# HIC_Board.net
KiCad netlist of a schematic drawn in EAGLE
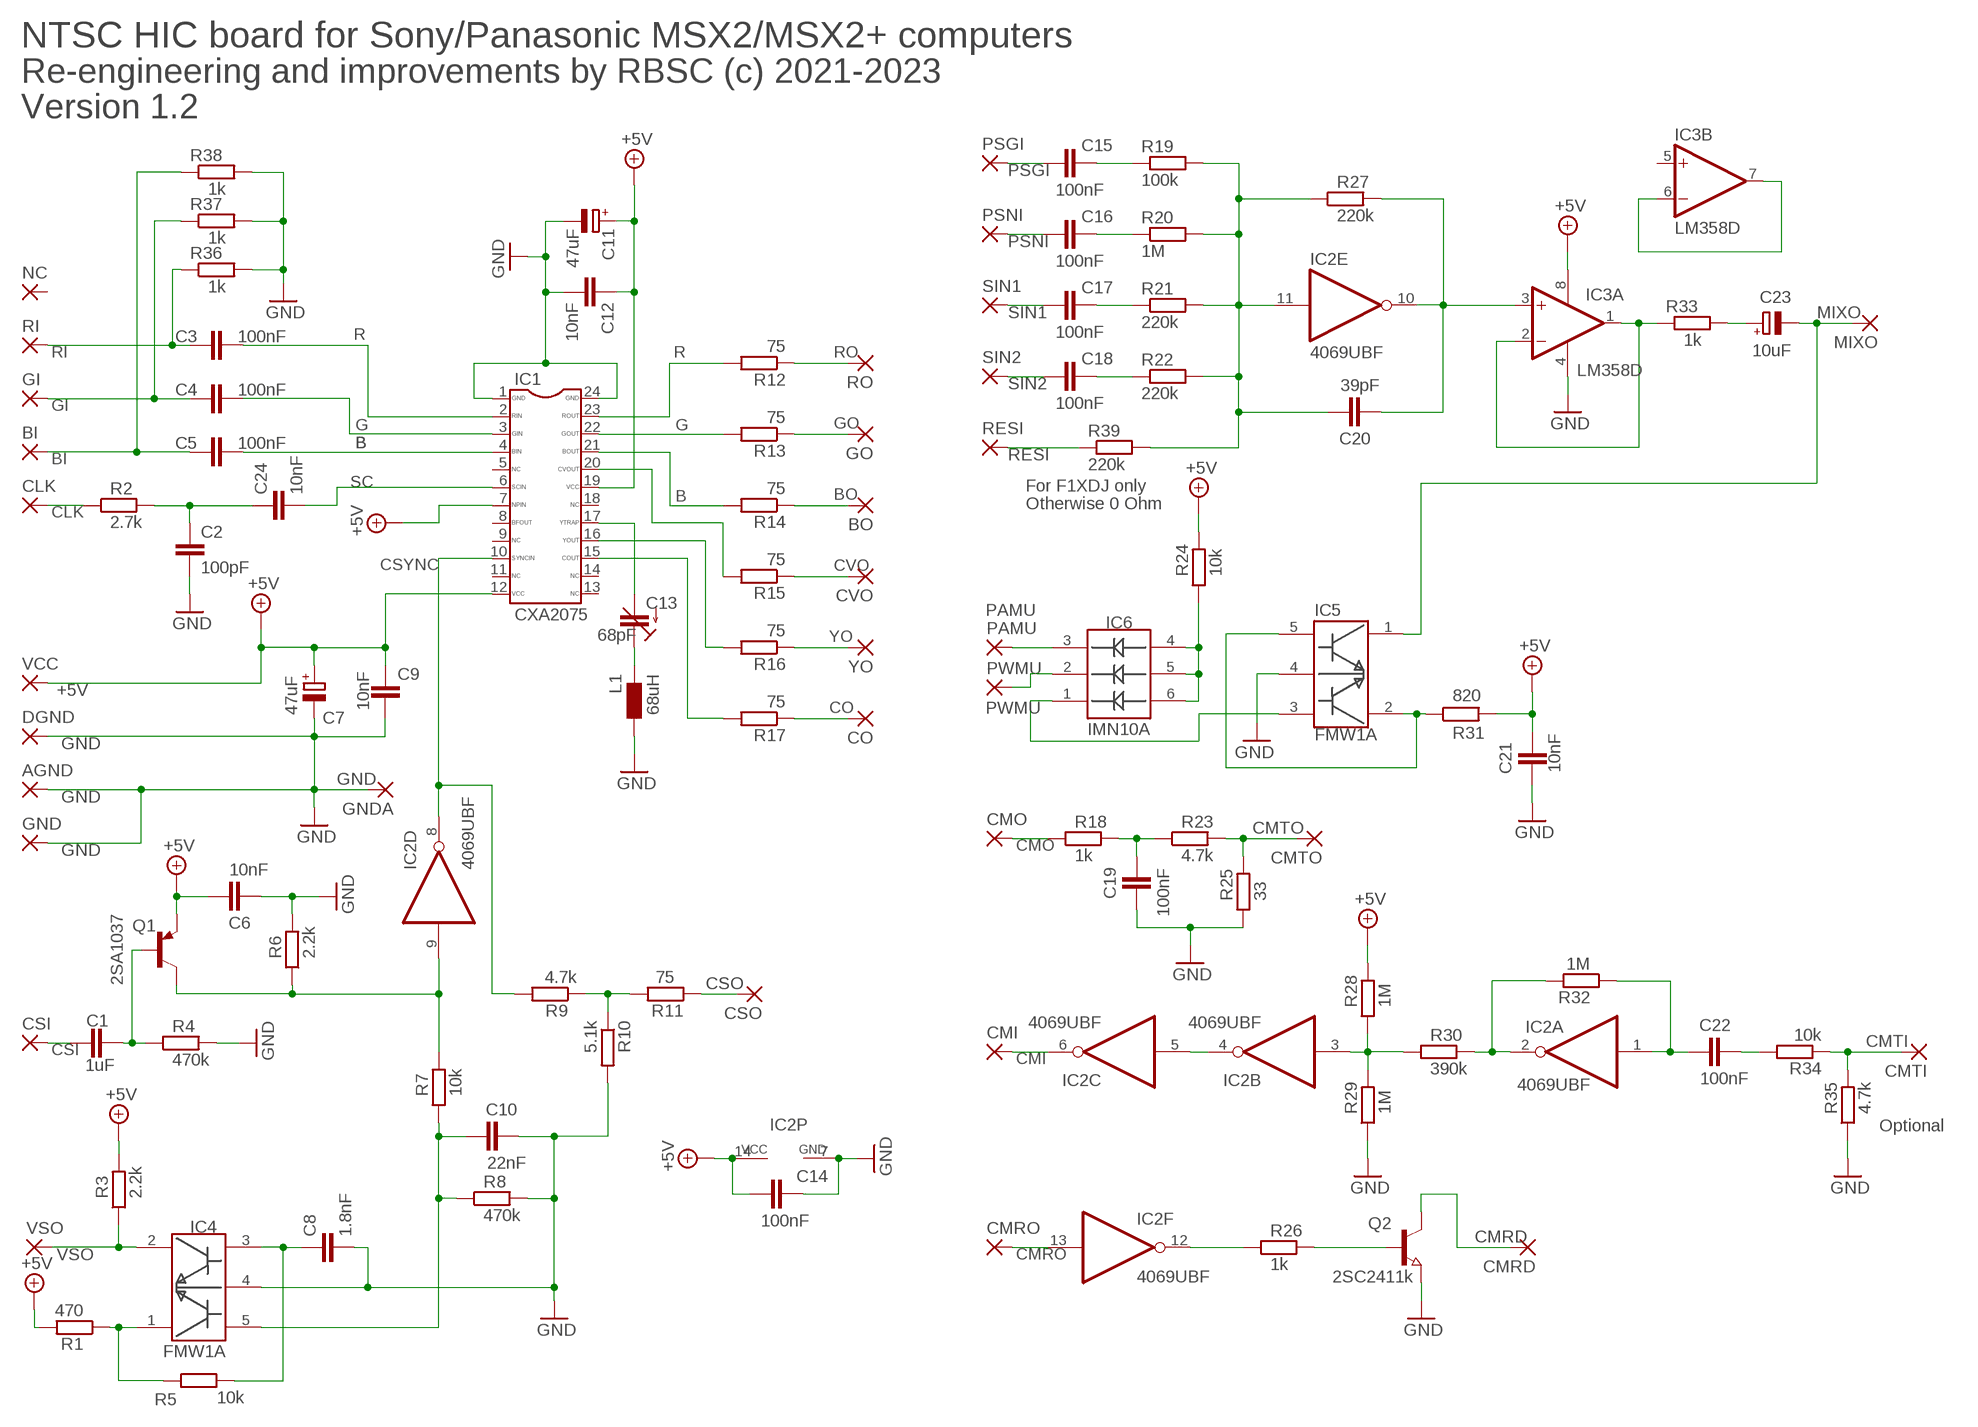
[diagram p0: schematic, sheet 1]

(export (version "E")
  (design (tool "Eeschema 10.0.6"))
  (components
    (comp (ref "AGND")
      (value "HICPADSMD")
      (footprint "eagle-import:SMD1,27-2,54")
      (libsource (lib "eagle-import") (part "HICPADSMD"))
    )
    (comp (ref "BI")
      (value "HICPADSMD")
      (footprint "eagle-import:SMD1,27-2,54")
      (libsource (lib "eagle-import") (part "HICPADSMD"))
    )
    (comp (ref "BO")
      (value "HICPADSMD")
      (footprint "eagle-import:SMD1,27-2,54")
      (libsource (lib "eagle-import") (part "HICPADSMD"))
    )
    (comp (ref "C1")
      (value "1uF")
      (footprint "eagle-import:C1210")
      (libsource (lib "eagle-import") (part "C-EUC1210"))
    )
    (comp (ref "C2")
      (value "100pF")
      (footprint "eagle-import:C0805")
      (libsource (lib "eagle-import") (part "C-EUC0805"))
    )
    (comp (ref "C3")
      (value "100nF")
      (footprint "eagle-import:C0805")
      (libsource (lib "eagle-import") (part "C-EUC0805"))
    )
    (comp (ref "C4")
      (value "100nF")
      (footprint "eagle-import:C0805")
      (libsource (lib "eagle-import") (part "C-EUC0805"))
    )
    (comp (ref "C5")
      (value "100nF")
      (footprint "eagle-import:C0805")
      (libsource (lib "eagle-import") (part "C-EUC0805"))
    )
    (comp (ref "C6")
      (value "10nF")
      (footprint "eagle-import:C0805")
      (libsource (lib "eagle-import") (part "C-EUC0805"))
    )
    (comp (ref "C7")
      (value "47uF")
      (footprint "eagle-import:SMC_B")
      (libsource (lib "eagle-import") (part "CPOL-EUSMCB"))
    )
    (comp (ref "C8")
      (value "1.8nF")
      (footprint "eagle-import:C0805")
      (libsource (lib "eagle-import") (part "C-EUC0805"))
    )
    (comp (ref "C9")
      (value "10nF")
      (footprint "eagle-import:C0805")
      (libsource (lib "eagle-import") (part "C-EUC0805"))
    )
    (comp (ref "C10")
      (value "22nF")
      (footprint "eagle-import:C0805")
      (libsource (lib "eagle-import") (part "C-EUC0805"))
    )
    (comp (ref "C11")
      (value "47uF")
      (footprint "eagle-import:SMC_B")
      (libsource (lib "eagle-import") (part "CPOL-EUSMCB"))
    )
    (comp (ref "C12")
      (value "10nF")
      (footprint "eagle-import:C0805")
      (libsource (lib "eagle-import") (part "C-EUC0805"))
    )
    (comp (ref "C13")
      (value "68pF")
      (footprint "eagle-import:CTRIMTZ03")
      (libsource (lib "eagle-import") (part "C-TRIMMTZ03"))
    )
    (comp (ref "C14")
      (value "100nF")
      (footprint "eagle-import:C0805")
      (libsource (lib "eagle-import") (part "C-EUC0805"))
    )
    (comp (ref "C15")
      (value "100nF")
      (footprint "eagle-import:C0805")
      (libsource (lib "eagle-import") (part "C-EUC0805"))
    )
    (comp (ref "C16")
      (value "100nF")
      (footprint "eagle-import:C0805")
      (libsource (lib "eagle-import") (part "C-EUC0805"))
    )
    (comp (ref "C17")
      (value "100nF")
      (footprint "eagle-import:C0805")
      (libsource (lib "eagle-import") (part "C-EUC0805"))
    )
    (comp (ref "C18")
      (value "100nF")
      (footprint "eagle-import:C0805")
      (libsource (lib "eagle-import") (part "C-EUC0805"))
    )
    (comp (ref "C19")
      (value "100nF")
      (footprint "eagle-import:C0805")
      (libsource (lib "eagle-import") (part "C-EUC0805"))
    )
    (comp (ref "C20")
      (value "39pF")
      (footprint "eagle-import:C0805")
      (libsource (lib "eagle-import") (part "C-EUC0805"))
    )
    (comp (ref "C21")
      (value "10nF")
      (footprint "eagle-import:C0805")
      (libsource (lib "eagle-import") (part "C-EUC0805"))
    )
    (comp (ref "C22")
      (value "100nF")
      (footprint "eagle-import:C0805")
      (libsource (lib "eagle-import") (part "C-EUC0805"))
    )
    (comp (ref "C23")
      (value "10uF")
      (footprint "eagle-import:SMC_B")
      (libsource (lib "eagle-import") (part "CPOL-EUSMCB"))
    )
    (comp (ref "C24")
      (value "10nF")
      (footprint "eagle-import:C0805")
      (libsource (lib "eagle-import") (part "C-EUC0805"))
    )
    (comp (ref "CLK")
      (value "HICPADSMD")
      (footprint "eagle-import:SMD1,27-2,54")
      (libsource (lib "eagle-import") (part "HICPADSMD"))
    )
    (comp (ref "CMI")
      (value "HICPADSMD")
      (footprint "eagle-import:SMD1,27-2,54")
      (libsource (lib "eagle-import") (part "HICPADSMD"))
    )
    (comp (ref "CMO")
      (value "HICPADSMD")
      (footprint "eagle-import:SMD1,27-2,54")
      (libsource (lib "eagle-import") (part "HICPADSMD"))
    )
    (comp (ref "CMRD")
      (value "HICPADSMD")
      (footprint "eagle-import:SMD1,27-2,54")
      (libsource (lib "eagle-import") (part "HICPADSMD"))
    )
    (comp (ref "CMRO")
      (value "HICPADSMD")
      (footprint "eagle-import:SMD1,27-2,54")
      (libsource (lib "eagle-import") (part "HICPADSMD"))
    )
    (comp (ref "CMTI")
      (value "HICPADSMD")
      (footprint "eagle-import:SMD1,27-2,54")
      (libsource (lib "eagle-import") (part "HICPADSMD"))
    )
    (comp (ref "CMTO")
      (value "HICPADSMD")
      (footprint "eagle-import:SMD1,27-2,54")
      (libsource (lib "eagle-import") (part "HICPADSMD"))
    )
    (comp (ref "CO")
      (value "HICPADSMD")
      (footprint "eagle-import:SMD1,27-2,54")
      (libsource (lib "eagle-import") (part "HICPADSMD"))
    )
    (comp (ref "CSI")
      (value "HICPADSMD")
      (footprint "eagle-import:SMD1,27-2,54")
      (libsource (lib "eagle-import") (part "HICPADSMD"))
    )
    (comp (ref "CSO")
      (value "HICPADSMD")
      (footprint "eagle-import:SMD1,27-2,54")
      (libsource (lib "eagle-import") (part "HICPADSMD"))
    )
    (comp (ref "CVO")
      (value "HICPADSMD")
      (footprint "eagle-import:SMD1,27-2,54")
      (libsource (lib "eagle-import") (part "HICPADSMD"))
    )
    (comp (ref "DGND")
      (value "HICPADSMD")
      (footprint "eagle-import:SMD1,27-2,54")
      (libsource (lib "eagle-import") (part "HICPADSMD"))
    )
    (comp (ref "GI")
      (value "HICPADSMD")
      (footprint "eagle-import:SMD1,27-2,54")
      (libsource (lib "eagle-import") (part "HICPADSMD"))
    )
    (comp (ref "GND")
      (value "HICPADSMD")
      (footprint "eagle-import:SMD1,27-2,54")
      (libsource (lib "eagle-import") (part "HICPADSMD"))
    )
    (comp (ref "GNDA")
      (value "HICPADSMD")
      (footprint "eagle-import:SMD1,27-2,54")
      (libsource (lib "eagle-import") (part "HICPADSMD"))
    )
    (comp (ref "GO")
      (value "HICPADSMD")
      (footprint "eagle-import:SMD1,27-2,54")
      (libsource (lib "eagle-import") (part "HICPADSMD"))
    )
    (comp (ref "IC1")
      (value "CXA2075")
      (footprint "eagle-import:SOP24")
      (libsource (lib "eagle-import") (part "CXA2075"))
    )
    (comp (ref "IC2")
      (value "4069UBF")
      (footprint "eagle-import:SO14")
      (libsource (lib "eagle-import") (part "7404DHCT"))
    )
    (comp (ref "IC3")
      (value "LM358D")
      (footprint "eagle-import:SO08")
      (libsource (lib "eagle-import") (part "LM358D"))
    )
    (comp (ref "IC4")
      (value "FMW1A")
      (footprint "eagle-import:SMT5")
      (libsource (lib "eagle-import") (part "FMW1A"))
    )
    (comp (ref "IC5")
      (value "FMW1A")
      (footprint "eagle-import:SMT5")
      (libsource (lib "eagle-import") (part "FMW1A"))
    )
    (comp (ref "IC6")
      (value "IMN10A")
      (footprint "eagle-import:SMT6")
      (libsource (lib "eagle-import") (part "IMN10A"))
    )
    (comp (ref "L1")
      (value "68uH")
      (footprint "eagle-import:L3225M")
      (libsource (lib "eagle-import") (part "LL3225M"))
    )
    (comp (ref "MIXO")
      (value "HICPADSMD")
      (footprint "eagle-import:SMD1,27-2,54")
      (libsource (lib "eagle-import") (part "HICPADSMD"))
    )
    (comp (ref "NC")
      (value "HICPADSMD")
      (footprint "eagle-import:SMD1,27-2,54")
      (libsource (lib "eagle-import") (part "HICPADSMD"))
    )
    (comp (ref "PAMU")
      (value "HICPADSMD")
      (footprint "eagle-import:SMD1,27-2,54")
      (libsource (lib "eagle-import") (part "HICPADSMD"))
    )
    (comp (ref "PSGI")
      (value "HICPADSMD")
      (footprint "eagle-import:SMD1,27-2,54")
      (libsource (lib "eagle-import") (part "HICPADSMD"))
    )
    (comp (ref "PSNI")
      (value "HICPADSMD")
      (footprint "eagle-import:SMD1,27-2,54")
      (libsource (lib "eagle-import") (part "HICPADSMD"))
    )
    (comp (ref "PWMU")
      (value "HICPADSMD")
      (footprint "eagle-import:SMD1,27-2,54")
      (libsource (lib "eagle-import") (part "HICPADSMD"))
    )
    (comp (ref "Q1")
      (value "2SA1037")
      (footprint "eagle-import:SOT23")
      (libsource (lib "eagle-import") (part "BCX71SMD"))
    )
    (comp (ref "Q2")
      (value "2SC2411k")
      (footprint "eagle-import:SOT23")
      (libsource (lib "eagle-import") (part "NPN-TRANSISTOR_SOT23"))
    )
    (comp (ref "R1")
      (value "470")
      (footprint "eagle-import:R0805")
      (libsource (lib "eagle-import") (part "R-EU_R0805"))
    )
    (comp (ref "R2")
      (value "2.7k")
      (footprint "eagle-import:R0805")
      (libsource (lib "eagle-import") (part "R-EU_R0805"))
    )
    (comp (ref "R3")
      (value "2.2k")
      (footprint "eagle-import:R0805")
      (libsource (lib "eagle-import") (part "R-EU_R0805"))
    )
    (comp (ref "R4")
      (value "470k")
      (footprint "eagle-import:R0805")
      (libsource (lib "eagle-import") (part "R-EU_R0805"))
    )
    (comp (ref "R5")
      (value "10k")
      (footprint "eagle-import:R0805")
      (libsource (lib "eagle-import") (part "R-EU_R0805"))
    )
    (comp (ref "R6")
      (value "2.2k")
      (footprint "eagle-import:R0805")
      (libsource (lib "eagle-import") (part "R-EU_R0805"))
    )
    (comp (ref "R7")
      (value "10k")
      (footprint "eagle-import:R0805")
      (libsource (lib "eagle-import") (part "R-EU_R0805"))
    )
    (comp (ref "R8")
      (value "470k")
      (footprint "eagle-import:R0805")
      (libsource (lib "eagle-import") (part "R-EU_R0805"))
    )
    (comp (ref "R9")
      (value "4.7k")
      (footprint "eagle-import:R0805")
      (libsource (lib "eagle-import") (part "R-EU_R0805"))
    )
    (comp (ref "R10")
      (value "5.1k")
      (footprint "eagle-import:R0805")
      (libsource (lib "eagle-import") (part "R-EU_R0805"))
    )
    (comp (ref "R11")
      (value "75")
      (footprint "eagle-import:R0805")
      (libsource (lib "eagle-import") (part "R-EU_R0805"))
    )
    (comp (ref "R12")
      (value "75")
      (footprint "eagle-import:R0805")
      (libsource (lib "eagle-import") (part "R-EU_R0805"))
    )
    (comp (ref "R13")
      (value "75")
      (footprint "eagle-import:R0805")
      (libsource (lib "eagle-import") (part "R-EU_R0805"))
    )
    (comp (ref "R14")
      (value "75")
      (footprint "eagle-import:R0805")
      (libsource (lib "eagle-import") (part "R-EU_R0805"))
    )
    (comp (ref "R15")
      (value "75")
      (footprint "eagle-import:R0805")
      (libsource (lib "eagle-import") (part "R-EU_R0805"))
    )
    (comp (ref "R16")
      (value "75")
      (footprint "eagle-import:R0805")
      (libsource (lib "eagle-import") (part "R-EU_R0805"))
    )
    (comp (ref "R17")
      (value "75")
      (footprint "eagle-import:R0805")
      (libsource (lib "eagle-import") (part "R-EU_R0805"))
    )
    (comp (ref "R18")
      (value "1k")
      (footprint "eagle-import:R0805")
      (libsource (lib "eagle-import") (part "R-EU_R0805"))
    )
    (comp (ref "R19")
      (value "100k")
      (footprint "eagle-import:R0805")
      (libsource (lib "eagle-import") (part "R-EU_R0805"))
    )
    (comp (ref "R20")
      (value "1M")
      (footprint "eagle-import:R0805")
      (libsource (lib "eagle-import") (part "R-EU_R0805"))
    )
    (comp (ref "R21")
      (value "220k")
      (footprint "eagle-import:R0805")
      (libsource (lib "eagle-import") (part "R-EU_R0805"))
    )
    (comp (ref "R22")
      (value "220k")
      (footprint "eagle-import:R0805")
      (libsource (lib "eagle-import") (part "R-EU_R0805"))
    )
    (comp (ref "R23")
      (value "4.7k")
      (footprint "eagle-import:R0805")
      (libsource (lib "eagle-import") (part "R-EU_R0805"))
    )
    (comp (ref "R24")
      (value "10k")
      (footprint "eagle-import:R0805")
      (libsource (lib "eagle-import") (part "R-EU_R0805"))
    )
    (comp (ref "R25")
      (value "33")
      (footprint "eagle-import:R0805")
      (libsource (lib "eagle-import") (part "R-EU_R0805"))
    )
    (comp (ref "R26")
      (value "1k")
      (footprint "eagle-import:R0805")
      (libsource (lib "eagle-import") (part "R-EU_R0805"))
    )
    (comp (ref "R27")
      (value "220k")
      (footprint "eagle-import:R0805")
      (libsource (lib "eagle-import") (part "R-EU_R0805"))
    )
    (comp (ref "R28")
      (value "1M")
      (footprint "eagle-import:R0805")
      (libsource (lib "eagle-import") (part "R-EU_R0805"))
    )
    (comp (ref "R29")
      (value "1M")
      (footprint "eagle-import:R0805")
      (libsource (lib "eagle-import") (part "R-EU_R0805"))
    )
    (comp (ref "R30")
      (value "390k")
      (footprint "eagle-import:R0805")
      (libsource (lib "eagle-import") (part "R-EU_R0805"))
    )
    (comp (ref "R31")
      (value "820")
      (footprint "eagle-import:R0805")
      (libsource (lib "eagle-import") (part "R-EU_R0805"))
    )
    (comp (ref "R32")
      (value "1M")
      (footprint "eagle-import:R0805")
      (libsource (lib "eagle-import") (part "R-EU_R0805"))
    )
    (comp (ref "R33")
      (value "1k")
      (footprint "eagle-import:R0805")
      (libsource (lib "eagle-import") (part "R-EU_R0805"))
    )
    (comp (ref "R34")
      (value "10k")
      (footprint "eagle-import:R0805")
      (libsource (lib "eagle-import") (part "R-EU_R0805"))
    )
    (comp (ref "R35")
      (value "4.7k")
      (footprint "eagle-import:R0805")
      (libsource (lib "eagle-import") (part "R-EU_R0805"))
    )
    (comp (ref "R36")
      (value "1k")
      (footprint "eagle-import:R0805")
      (libsource (lib "eagle-import") (part "R-EU_R0805"))
    )
    (comp (ref "R37")
      (value "1k")
      (footprint "eagle-import:R0805")
      (libsource (lib "eagle-import") (part "R-EU_R0805"))
    )
    (comp (ref "R38")
      (value "1k")
      (footprint "eagle-import:R0805")
      (libsource (lib "eagle-import") (part "R-EU_R0805"))
    )
    (comp (ref "R39")
      (value "220k")
      (footprint "eagle-import:R0805")
      (libsource (lib "eagle-import") (part "R-EU_R0805"))
    )
    (comp (ref "RESI")
      (value "HICPADSMD")
      (footprint "eagle-import:SMD1,27-2,54")
      (libsource (lib "eagle-import") (part "HICPADSMD"))
    )
    (comp (ref "RI")
      (value "HICPADSMD")
      (footprint "eagle-import:SMD1,27-2,54")
      (libsource (lib "eagle-import") (part "HICPADSMD"))
    )
    (comp (ref "RO")
      (value "HICPADSMD")
      (footprint "eagle-import:SMD1,27-2,54")
      (libsource (lib "eagle-import") (part "HICPADSMD"))
    )
    (comp (ref "SIN1")
      (value "HICPADSMD")
      (footprint "eagle-import:SMD1,27-2,54")
      (libsource (lib "eagle-import") (part "HICPADSMD"))
    )
    (comp (ref "SIN2")
      (value "HICPADSMD")
      (footprint "eagle-import:SMD1,27-2,54")
      (libsource (lib "eagle-import") (part "HICPADSMD"))
    )
    (comp (ref "VCC")
      (value "HICPADSMD")
      (footprint "eagle-import:SMD1,27-2,54")
      (libsource (lib "eagle-import") (part "HICPADSMD"))
    )
    (comp (ref "VSO")
      (value "HICPADSMD")
      (footprint "eagle-import:SMD1,27-2,54")
      (libsource (lib "eagle-import") (part "HICPADSMD"))
    )
    (comp (ref "YO")
      (value "HICPADSMD")
      (footprint "eagle-import:SMD1,27-2,54")
      (libsource (lib "eagle-import") (part "HICPADSMD"))
    )
  )
  (nets
    (net (code "1") (name "+5V") (class "Default")
      (node (ref "C11") (pin "+") (pinfunction "+_+") (pintype "passive"))
      (node (ref "C12") (pin "1") (pinfunction "1_1") (pintype "passive"))
      (node (ref "C14") (pin "2") (pinfunction "2_2") (pintype "passive"))
      (node (ref "C21") (pin "2") (pinfunction "2_2") (pintype "passive"))
      (node (ref "C6") (pin "1") (pinfunction "1_1") (pintype "passive"))
      (node (ref "C7") (pin "+") (pinfunction "+_+") (pintype "passive"))
      (node (ref "C9") (pin "2") (pinfunction "2_2") (pintype "passive"))
      (node (ref "IC1") (pin "12") (pinfunction "12_12") (pintype "passive"))
      (node (ref "IC1") (pin "19") (pinfunction "19_19") (pintype "passive"))
      (node (ref "IC1") (pin "7") (pinfunction "7_7") (pintype "passive"))
      (node (ref "IC2") (pin "14") (pinfunction "VCC_14") (pintype "power_in"))
      (node (ref "IC3") (pin "8") (pinfunction "V+_8") (pintype "power_in"))
      (node (ref "Q1") (pin "2") (pinfunction "E_2") (pintype "passive"))
      (node (ref "R1") (pin "2") (pinfunction "2_2") (pintype "passive"))
      (node (ref "R24") (pin "2") (pinfunction "2_2") (pintype "passive"))
      (node (ref "R28") (pin "2") (pinfunction "2_2") (pintype "passive"))
      (node (ref "R3") (pin "2") (pinfunction "2_2") (pintype "passive"))
      (node (ref "R31") (pin "2") (pinfunction "2_2") (pintype "passive"))
      (node (ref "VCC") (pin "1") (pinfunction "P_1") (pintype "bidirectional"))
    )
    (net (code "2") (name "/CMRD") (class "Default")
      (node (ref "CMRD") (pin "1") (pinfunction "P_1") (pintype "bidirectional"))
      (node (ref "Q2") (pin "3") (pinfunction "C_3") (pintype "passive"))
    )
    (net (code "3") (name "/CMTI") (class "Default")
      (node (ref "CMTI") (pin "1") (pinfunction "P_1") (pintype "bidirectional"))
      (node (ref "R34") (pin "1") (pinfunction "1_1") (pintype "passive"))
      (node (ref "R35") (pin "2") (pinfunction "2_2") (pintype "passive"))
    )
    (net (code "4") (name "/CMTO") (class "Default")
      (node (ref "CMTO") (pin "1") (pinfunction "P_1") (pintype "bidirectional"))
      (node (ref "R23") (pin "2") (pinfunction "2_2") (pintype "passive"))
      (node (ref "R25") (pin "2") (pinfunction "2_2") (pintype "passive"))
    )
    (net (code "5") (name "/CSO") (class "Default")
      (node (ref "CSO") (pin "1") (pinfunction "P_1") (pintype "bidirectional"))
      (node (ref "R11") (pin "1") (pinfunction "1_1") (pintype "passive"))
    )
    (net (code "6") (name "/MIXO") (class "Default")
      (node (ref "C23") (pin "-") (pinfunction "-_-") (pintype "passive"))
      (node (ref "IC5") (pin "1") (pinfunction "P$1_1") (pintype "bidirectional"))
      (node (ref "MIXO") (pin "1") (pinfunction "P_1") (pintype "bidirectional"))
    )
    (net (code "7") (name "/PAMU") (class "Default")
      (node (ref "IC6") (pin "3") (pinfunction "P$3_3") (pintype "bidirectional"))
      (node (ref "PAMU") (pin "1") (pinfunction "P_1") (pintype "bidirectional"))
    )
    (net (code "8") (name "/PSGI") (class "Default")
      (node (ref "C15") (pin "1") (pinfunction "1_1") (pintype "passive"))
      (node (ref "PSGI") (pin "1") (pinfunction "P_1") (pintype "bidirectional"))
    )
    (net (code "9") (name "/PSNI") (class "Default")
      (node (ref "C16") (pin "1") (pinfunction "1_1") (pintype "passive"))
      (node (ref "PSNI") (pin "1") (pinfunction "P_1") (pintype "bidirectional"))
    )
    (net (code "10") (name "/PWMU") (class "Default")
      (node (ref "IC6") (pin "2") (pinfunction "P$2_2") (pintype "bidirectional"))
      (node (ref "PWMU") (pin "1") (pinfunction "P_1") (pintype "bidirectional"))
    )
    (net (code "11") (name "/RESI") (class "Default")
      (node (ref "C20") (pin "1") (pinfunction "1_1") (pintype "passive"))
      (node (ref "IC2") (pin "11") (pinfunction "I_11") (pintype "input"))
      (node (ref "R19") (pin "2") (pinfunction "2_2") (pintype "passive"))
      (node (ref "R20") (pin "2") (pinfunction "2_2") (pintype "passive"))
      (node (ref "R21") (pin "2") (pinfunction "2_2") (pintype "passive"))
      (node (ref "R22") (pin "2") (pinfunction "2_2") (pintype "passive"))
      (node (ref "R27") (pin "1") (pinfunction "1_1") (pintype "passive"))
      (node (ref "R39") (pin "2") (pinfunction "2_2") (pintype "passive"))
    )
    (net (code "12") (name "/SIN1") (class "Default")
      (node (ref "C17") (pin "1") (pinfunction "1_1") (pintype "passive"))
      (node (ref "SIN1") (pin "1") (pinfunction "P_1") (pintype "bidirectional"))
    )
    (net (code "13") (name "/SIN2") (class "Default")
      (node (ref "C18") (pin "1") (pinfunction "1_1") (pintype "passive"))
      (node (ref "SIN2") (pin "1") (pinfunction "P_1") (pintype "bidirectional"))
    )
    (net (code "14") (name "/VSO") (class "Default")
      (node (ref "IC4") (pin "2") (pinfunction "P$2_2") (pintype "bidirectional"))
      (node (ref "R3") (pin "1") (pinfunction "1_1") (pintype "passive"))
      (node (ref "VSO") (pin "1") (pinfunction "P_1") (pintype "bidirectional"))
    )
    (net (code "15") (name "GND") (class "Default")
      (node (ref "AGND") (pin "1") (pinfunction "P_1") (pintype "bidirectional"))
      (node (ref "C10") (pin "2") (pinfunction "2_2") (pintype "passive"))
      (node (ref "C11") (pin "-") (pinfunction "-_-") (pintype "passive"))
      (node (ref "C12") (pin "2") (pinfunction "2_2") (pintype "passive"))
      (node (ref "C14") (pin "1") (pinfunction "1_1") (pintype "passive"))
      (node (ref "C19") (pin "2") (pinfunction "2_2") (pintype "passive"))
      (node (ref "C2") (pin "1") (pinfunction "1_1") (pintype "passive"))
      (node (ref "C21") (pin "1") (pinfunction "1_1") (pintype "passive"))
      (node (ref "C6") (pin "2") (pinfunction "2_2") (pintype "passive"))
      (node (ref "C7") (pin "-") (pinfunction "-_-") (pintype "passive"))
      (node (ref "C8") (pin "1") (pinfunction "1_1") (pintype "passive"))
      (node (ref "C9") (pin "1") (pinfunction "1_1") (pintype "passive"))
      (node (ref "DGND") (pin "1") (pinfunction "P_1") (pintype "bidirectional"))
      (node (ref "GND") (pin "1") (pinfunction "P_1") (pintype "bidirectional"))
      (node (ref "GNDA") (pin "1") (pinfunction "P_1") (pintype "bidirectional"))
      (node (ref "IC1") (pin "1") (pinfunction "1_1") (pintype "passive"))
      (node (ref "IC1") (pin "24") (pinfunction "24_24") (pintype "passive"))
      (node (ref "IC2") (pin "7") (pinfunction "GND_7") (pintype "power_in"))
      (node (ref "IC3") (pin "4") (pinfunction "V-_4") (pintype "power_in"))
      (node (ref "IC4") (pin "4") (pinfunction "P$4_4") (pintype "bidirectional"))
      (node (ref "IC5") (pin "4") (pinfunction "P$4_4") (pintype "bidirectional"))
      (node (ref "L1") (pin "1") (pinfunction "1_1") (pintype "passive"))
      (node (ref "Q2") (pin "2") (pinfunction "E_2") (pintype "passive"))
      (node (ref "R10") (pin "2") (pinfunction "2_2") (pintype "passive"))
      (node (ref "R25") (pin "1") (pinfunction "1_1") (pintype "passive"))
      (node (ref "R29") (pin "1") (pinfunction "1_1") (pintype "passive"))
      (node (ref "R35") (pin "1") (pinfunction "1_1") (pintype "passive"))
      (node (ref "R36") (pin "2") (pinfunction "2_2") (pintype "passive"))
      (node (ref "R37") (pin "2") (pinfunction "2_2") (pintype "passive"))
      (node (ref "R38") (pin "2") (pinfunction "2_2") (pintype "passive"))
      (node (ref "R4") (pin "2") (pinfunction "2_2") (pintype "passive"))
      (node (ref "R6") (pin "2") (pinfunction "2_2") (pintype "passive"))
      (node (ref "R8") (pin "2") (pinfunction "2_2") (pintype "passive"))
    )
    (net (code "16") (name "Net-(BI-P)") (class "Default")
      (node (ref "BI") (pin "1") (pinfunction "P_1") (pintype "bidirectional"))
      (node (ref "C5") (pin "1") (pinfunction "1_1") (pintype "passive"))
      (node (ref "R38") (pin "1") (pinfunction "1_1") (pintype "passive"))
    )
    (net (code "17") (name "Net-(BO-P)") (class "Default")
      (node (ref "BO") (pin "1") (pinfunction "P_1") (pintype "bidirectional"))
      (node (ref "R14") (pin "1") (pinfunction "1_1") (pintype "passive"))
    )
    (net (code "18") (name "Net-(C2-Pad2)") (class "Default")
      (node (ref "C2") (pin "2") (pinfunction "2_2") (pintype "passive"))
      (node (ref "C24") (pin "2") (pinfunction "2_2") (pintype "passive"))
      (node (ref "R2") (pin "2") (pinfunction "2_2") (pintype "passive"))
    )
    (net (code "19") (name "Net-(C3-Pad2)") (class "Default")
      (node (ref "C3") (pin "2") (pinfunction "2_2") (pintype "passive"))
      (node (ref "IC1") (pin "2") (pinfunction "2_2") (pintype "passive"))
    )
    (net (code "20") (name "Net-(C4-Pad2)") (class "Default")
      (node (ref "C4") (pin "2") (pinfunction "2_2") (pintype "passive"))
      (node (ref "IC1") (pin "3") (pinfunction "3_3") (pintype "passive"))
    )
    (net (code "21") (name "Net-(C5-Pad2)") (class "Default")
      (node (ref "C5") (pin "2") (pinfunction "2_2") (pintype "passive"))
      (node (ref "IC1") (pin "4") (pinfunction "4_4") (pintype "passive"))
    )
    (net (code "22") (name "Net-(C13-A)") (class "Default")
      (node (ref "C13") (pin "2") (pinfunction "A_2") (pintype "passive"))
      (node (ref "IC1") (pin "17") (pinfunction "17_17") (pintype "passive"))
    )
    (net (code "23") (name "Net-(C13-E)") (class "Default")
      (node (ref "C13") (pin "1") (pinfunction "E_1") (pintype "passive"))
      (node (ref "L1") (pin "2") (pinfunction "2_2") (pintype "passive"))
    )
    (net (code "24") (name "Net-(C15-Pad2)") (class "Default")
      (node (ref "C15") (pin "2") (pinfunction "2_2") (pintype "passive"))
      (node (ref "R19") (pin "1") (pinfunction "1_1") (pintype "passive"))
    )
    (net (code "25") (name "Net-(C16-Pad2)") (class "Default")
      (node (ref "C16") (pin "2") (pinfunction "2_2") (pintype "passive"))
      (node (ref "R20") (pin "1") (pinfunction "1_1") (pintype "passive"))
    )
    (net (code "26") (name "Net-(C17-Pad2)") (class "Default")
      (node (ref "C17") (pin "2") (pinfunction "2_2") (pintype "passive"))
      (node (ref "R21") (pin "1") (pinfunction "1_1") (pintype "passive"))
    )
    (net (code "27") (name "Net-(C18-Pad2)") (class "Default")
      (node (ref "C18") (pin "2") (pinfunction "2_2") (pintype "passive"))
      (node (ref "R22") (pin "1") (pinfunction "1_1") (pintype "passive"))
    )
    (net (code "28") (name "Net-(C19-Pad1)") (class "Default")
      (node (ref "C19") (pin "1") (pinfunction "1_1") (pintype "passive"))
      (node (ref "R18") (pin "2") (pinfunction "2_2") (pintype "passive"))
      (node (ref "R23") (pin "1") (pinfunction "1_1") (pintype "passive"))
    )
    (net (code "29") (name "Net-(C22-Pad2)") (class "Default")
      (node (ref "C22") (pin "2") (pinfunction "2_2") (pintype "passive"))
      (node (ref "R34") (pin "2") (pinfunction "2_2") (pintype "passive"))
    )
    (net (code "30") (name "Net-(C23-Pad+)") (class "Default")
      (node (ref "C23") (pin "+") (pinfunction "+_+") (pintype "passive"))
      (node (ref "R33") (pin "2") (pinfunction "2_2") (pintype "passive"))
    )
    (net (code "31") (name "Net-(C24-Pad1)") (class "Default")
      (node (ref "C24") (pin "1") (pinfunction "1_1") (pintype "passive"))
      (node (ref "IC1") (pin "6") (pinfunction "6_6") (pintype "passive"))
    )
    (net (code "32") (name "Net-(CLK-P)") (class "Default")
      (node (ref "CLK") (pin "1") (pinfunction "P_1") (pintype "bidirectional"))
      (node (ref "R2") (pin "1") (pinfunction "1_1") (pintype "passive"))
    )
    (net (code "33") (name "Net-(CMI-P)") (class "Default")
      (node (ref "CMI") (pin "1") (pinfunction "P_1") (pintype "bidirectional"))
      (node (ref "IC2") (pin "6") (pinfunction "O_6") (pintype "output"))
    )
    (net (code "34") (name "Net-(CMO-P)") (class "Default")
      (node (ref "CMO") (pin "1") (pinfunction "P_1") (pintype "bidirectional"))
      (node (ref "R18") (pin "1") (pinfunction "1_1") (pintype "passive"))
    )
    (net (code "35") (name "Net-(CMRO-P)") (class "Default")
      (node (ref "CMRO") (pin "1") (pinfunction "P_1") (pintype "bidirectional"))
      (node (ref "IC2") (pin "13") (pinfunction "I_13") (pintype "input"))
    )
    (net (code "36") (name "Net-(CO-P)") (class "Default")
      (node (ref "CO") (pin "1") (pinfunction "P_1") (pintype "bidirectional"))
      (node (ref "R17") (pin "1") (pinfunction "1_1") (pintype "passive"))
    )
    (net (code "37") (name "Net-(CSI-P)") (class "Default")
      (node (ref "C1") (pin "2") (pinfunction "2_2") (pintype "passive"))
      (node (ref "CSI") (pin "1") (pinfunction "P_1") (pintype "bidirectional"))
    )
    (net (code "38") (name "Net-(CVO-P)") (class "Default")
      (node (ref "CVO") (pin "1") (pinfunction "P_1") (pintype "bidirectional"))
      (node (ref "R15") (pin "1") (pinfunction "1_1") (pintype "passive"))
    )
    (net (code "39") (name "Net-(GI-P)") (class "Default")
      (node (ref "C4") (pin "1") (pinfunction "1_1") (pintype "passive"))
      (node (ref "GI") (pin "1") (pinfunction "P_1") (pintype "bidirectional"))
      (node (ref "R37") (pin "1") (pinfunction "1_1") (pintype "passive"))
    )
    (net (code "40") (name "Net-(GO-P)") (class "Default")
      (node (ref "GO") (pin "1") (pinfunction "P_1") (pintype "bidirectional"))
      (node (ref "R13") (pin "1") (pinfunction "1_1") (pintype "passive"))
    )
    (net (code "41") (name "Net-(IC1-Pad15)") (class "Default")
      (node (ref "IC1") (pin "15") (pinfunction "15_15") (pintype "passive"))
      (node (ref "R17") (pin "2") (pinfunction "2_2") (pintype "passive"))
    )
    (net (code "42") (name "Net-(IC1-Pad16)") (class "Default")
      (node (ref "IC1") (pin "16") (pinfunction "16_16") (pintype "passive"))
      (node (ref "R16") (pin "2") (pinfunction "2_2") (pintype "passive"))
    )
    (net (code "43") (name "Net-(IC1-Pad20)") (class "Default")
      (node (ref "IC1") (pin "20") (pinfunction "20_20") (pintype "passive"))
      (node (ref "R15") (pin "2") (pinfunction "2_2") (pintype "passive"))
    )
    (net (code "44") (name "Net-(IC1-Pad21)") (class "Default")
      (node (ref "IC1") (pin "21") (pinfunction "21_21") (pintype "passive"))
      (node (ref "R14") (pin "2") (pinfunction "2_2") (pintype "passive"))
    )
    (net (code "45") (name "Net-(IC1-Pad22)") (class "Default")
      (node (ref "IC1") (pin "22") (pinfunction "22_22") (pintype "passive"))
      (node (ref "R13") (pin "2") (pinfunction "2_2") (pintype "passive"))
    )
    (net (code "46") (name "Net-(IC1-Pad23)") (class "Default")
      (node (ref "IC1") (pin "23") (pinfunction "23_23") (pintype "passive"))
      (node (ref "R12") (pin "2") (pinfunction "2_2") (pintype "passive"))
    )
    (net (code "47") (name "Net-(IC2A-I)") (class "Default")
      (node (ref "C22") (pin "1") (pinfunction "1_1") (pintype "passive"))
      (node (ref "IC2") (pin "1") (pinfunction "I_1") (pintype "input"))
      (node (ref "R32") (pin "1") (pinfunction "1_1") (pintype "passive"))
    )
    (net (code "48") (name "Net-(IC2A-O)") (class "Default")
      (node (ref "IC2") (pin "2") (pinfunction "O_2") (pintype "output"))
      (node (ref "R30") (pin "2") (pinfunction "2_2") (pintype "passive"))
      (node (ref "R32") (pin "2") (pinfunction "2_2") (pintype "passive"))
    )
    (net (code "49") (name "Net-(IC2B-I)") (class "Default")
      (node (ref "IC2") (pin "3") (pinfunction "I_3") (pintype "input"))
      (node (ref "R28") (pin "1") (pinfunction "1_1") (pintype "passive"))
      (node (ref "R29") (pin "2") (pinfunction "2_2") (pintype "passive"))
      (node (ref "R30") (pin "1") (pinfunction "1_1") (pintype "passive"))
    )
    (net (code "50") (name "Net-(IC2B-O)") (class "Default")
      (node (ref "IC2") (pin "4") (pinfunction "O_4") (pintype "output"))
      (node (ref "IC2") (pin "5") (pinfunction "I_5") (pintype "input"))
    )
    (net (code "51") (name "Net-(IC2D-I)") (class "Default")
      (node (ref "IC2") (pin "9") (pinfunction "I_9") (pintype "input"))
      (node (ref "Q1") (pin "3") (pinfunction "C_3") (pintype "passive"))
      (node (ref "R6") (pin "1") (pinfunction "1_1") (pintype "passive"))
      (node (ref "R7") (pin "2") (pinfunction "2_2") (pintype "passive"))
    )
    (net (code "52") (name "Net-(IC2D-O)") (class "Default")
      (node (ref "IC1") (pin "10") (pinfunction "10_10") (pintype "passive"))
      (node (ref "IC2") (pin "8") (pinfunction "O_8") (pintype "output"))
      (node (ref "R9") (pin "2") (pinfunction "2_2") (pintype "passive"))
    )
    (net (code "53") (name "Net-(IC2E-O)") (class "Default")
      (node (ref "C20") (pin "2") (pinfunction "2_2") (pintype "passive"))
      (node (ref "IC2") (pin "10") (pinfunction "O_10") (pintype "output"))
      (node (ref "IC3") (pin "3") (pinfunction "+IN_3") (pintype "input"))
      (node (ref "R27") (pin "2") (pinfunction "2_2") (pintype "passive"))
    )
    (net (code "54") (name "Net-(IC2F-O)") (class "Default")
      (node (ref "IC2") (pin "12") (pinfunction "O_12") (pintype "output"))
      (node (ref "R26") (pin "1") (pinfunction "1_1") (pintype "passive"))
    )
    (net (code "55") (name "Net-(IC3A--IN)") (class "Default")
      (node (ref "IC3") (pin "1") (pinfunction "OUT_1") (pintype "output"))
      (node (ref "IC3") (pin "2") (pinfunction "-IN_2") (pintype "input"))
      (node (ref "R33") (pin "1") (pinfunction "1_1") (pintype "passive"))
    )
    (net (code "56") (name "Net-(IC3B--IN)") (class "Default")
      (node (ref "IC3") (pin "6") (pinfunction "-IN_6") (pintype "input"))
      (node (ref "IC3") (pin "7") (pinfunction "OUT_7") (pintype "output"))
    )
    (net (code "57") (name "Net-(IC4-P$1)") (class "Default")
      (node (ref "IC4") (pin "1") (pinfunction "P$1_1") (pintype "bidirectional"))
      (node (ref "R1") (pin "1") (pinfunction "1_1") (pintype "passive"))
      (node (ref "R5") (pin "1") (pinfunction "1_1") (pintype "passive"))
    )
    (net (code "58") (name "Net-(IC4-P$3)") (class "Default")
      (node (ref "C8") (pin "2") (pinfunction "2_2") (pintype "passive"))
      (node (ref "IC4") (pin "3") (pinfunction "P$3_3") (pintype "bidirectional"))
      (node (ref "R5") (pin "2") (pinfunction "2_2") (pintype "passive"))
    )
    (net (code "59") (name "Net-(IC4-P$5)") (class "Default")
      (node (ref "C10") (pin "1") (pinfunction "1_1") (pintype "passive"))
      (node (ref "IC4") (pin "5") (pinfunction "P$5_5") (pintype "bidirectional"))
      (node (ref "R7") (pin "1") (pinfunction "1_1") (pintype "passive"))
      (node (ref "R8") (pin "1") (pinfunction "1_1") (pintype "passive"))
    )
    (net (code "60") (name "Net-(IC5-P$2)") (class "Default")
      (node (ref "IC5") (pin "2") (pinfunction "P$2_2") (pintype "bidirectional"))
      (node (ref "IC5") (pin "5") (pinfunction "P$5_5") (pintype "bidirectional"))
      (node (ref "R31") (pin "1") (pinfunction "1_1") (pintype "passive"))
    )
    (net (code "61") (name "Net-(IC5-P$3)") (class "Default")
      (node (ref "IC5") (pin "3") (pinfunction "P$3_3") (pintype "bidirectional"))
      (node (ref "IC6") (pin "1") (pinfunction "P$1_1") (pintype "bidirectional"))
    )
    (net (code "62") (name "Net-(IC6-P$4)") (class "Default")
      (node (ref "IC6") (pin "4") (pinfunction "P$4_4") (pintype "bidirectional"))
      (node (ref "IC6") (pin "5") (pinfunction "P$5_5") (pintype "bidirectional"))
      (node (ref "IC6") (pin "6") (pinfunction "P$6_6") (pintype "bidirectional"))
      (node (ref "R24") (pin "1") (pinfunction "1_1") (pintype "passive"))
    )
    (net (code "63") (name "Net-(Q1-B)") (class "Default")
      (node (ref "C1") (pin "1") (pinfunction "1_1") (pintype "passive"))
      (node (ref "Q1") (pin "1") (pinfunction "B_1") (pintype "passive"))
      (node (ref "R4") (pin "1") (pinfunction "1_1") (pintype "passive"))
    )
    (net (code "64") (name "Net-(Q2-B)") (class "Default")
      (node (ref "Q2") (pin "1") (pinfunction "B_1") (pintype "passive"))
      (node (ref "R26") (pin "2") (pinfunction "2_2") (pintype "passive"))
    )
    (net (code "65") (name "Net-(R10-Pad1)") (class "Default")
      (node (ref "R10") (pin "1") (pinfunction "1_1") (pintype "passive"))
      (node (ref "R11") (pin "2") (pinfunction "2_2") (pintype "passive"))
      (node (ref "R9") (pin "1") (pinfunction "1_1") (pintype "passive"))
    )
    (net (code "66") (name "Net-(RESI-P)") (class "Default")
      (node (ref "R39") (pin "1") (pinfunction "1_1") (pintype "passive"))
      (node (ref "RESI") (pin "1") (pinfunction "P_1") (pintype "bidirectional"))
    )
    (net (code "67") (name "Net-(RI-P)") (class "Default")
      (node (ref "C3") (pin "1") (pinfunction "1_1") (pintype "passive"))
      (node (ref "R36") (pin "1") (pinfunction "1_1") (pintype "passive"))
      (node (ref "RI") (pin "1") (pinfunction "P_1") (pintype "bidirectional"))
    )
    (net (code "68") (name "Net-(RO-P)") (class "Default")
      (node (ref "R12") (pin "1") (pinfunction "1_1") (pintype "passive"))
      (node (ref "RO") (pin "1") (pinfunction "P_1") (pintype "bidirectional"))
    )
    (net (code "69") (name "Net-(YO-P)") (class "Default")
      (node (ref "R16") (pin "1") (pinfunction "1_1") (pintype "passive"))
      (node (ref "YO") (pin "1") (pinfunction "P_1") (pintype "bidirectional"))
    )
    (net (code "70") (name "unconnected-(IC1-Pad5)") (class "Default")
      (node (ref "IC1") (pin "5") (pinfunction "5_5") (pintype "passive"))
    )
    (net (code "71") (name "unconnected-(IC1-Pad8)") (class "Default")
      (node (ref "IC1") (pin "8") (pinfunction "8_8") (pintype "passive"))
    )
    (net (code "72") (name "unconnected-(IC1-Pad9)") (class "Default")
      (node (ref "IC1") (pin "9") (pinfunction "9_9") (pintype "passive"))
    )
    (net (code "73") (name "unconnected-(IC1-Pad11)") (class "Default")
      (node (ref "IC1") (pin "11") (pinfunction "11_11") (pintype "passive"))
    )
    (net (code "74") (name "unconnected-(IC1-Pad13)") (class "Default")
      (node (ref "IC1") (pin "13") (pinfunction "13_13") (pintype "passive"))
    )
    (net (code "75") (name "unconnected-(IC1-Pad14)") (class "Default")
      (node (ref "IC1") (pin "14") (pinfunction "14_14") (pintype "passive"))
    )
    (net (code "76") (name "unconnected-(IC1-Pad18)") (class "Default")
      (node (ref "IC1") (pin "18") (pinfunction "18_18") (pintype "passive"))
    )
    (net (code "77") (name "unconnected-(IC3B-+IN-Pad5)") (class "Default")
      (node (ref "IC3") (pin "5") (pinfunction "+IN_5") (pintype "input"))
    )
    (net (code "78") (name "unconnected-(NC-P-Pad1)") (class "Default")
      (node (ref "NC") (pin "1") (pinfunction "P_1") (pintype "bidirectional"))
    )
  )
)
